# n64-breakout.net
KiCad netlist of a schematic drawn in EAGLE
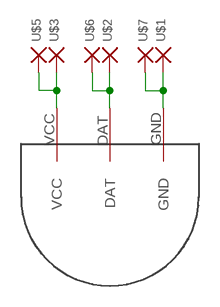
[diagram p0: schematic, sheet 1]

(export (version "E")
  (design (tool "Eeschema 10.0.6"))
  (components
    (comp (ref "U$1")
      (value "SMDPADSMD6080")
      (footprint "eagle-import:SMD6080")
      (libsource (lib "eagle-import") (part "SMDPADSMD6080"))
    )
    (comp (ref "U$2")
      (value "SMDPADSMD6080")
      (footprint "eagle-import:SMD6080")
      (libsource (lib "eagle-import") (part "SMDPADSMD6080"))
    )
    (comp (ref "U$3")
      (value "SMDPADSMD6080")
      (footprint "eagle-import:SMD6080")
      (libsource (lib "eagle-import") (part "SMDPADSMD6080"))
    )
    (comp (ref "U$4")
      (value "N64-CONNECTOR")
      (footprint "eagle-import:N64-CONNECTOR")
      (libsource (lib "eagle-import") (part "N64-CONNECTOR"))
    )
    (comp (ref "U$5")
      (value "SMDPADSMD6080")
      (footprint "eagle-import:SMD6080")
      (libsource (lib "eagle-import") (part "SMDPADSMD6080"))
    )
    (comp (ref "U$6")
      (value "SMDPADSMD6080")
      (footprint "eagle-import:SMD6080")
      (libsource (lib "eagle-import") (part "SMDPADSMD6080"))
    )
    (comp (ref "U$7")
      (value "SMDPADSMD6080")
      (footprint "eagle-import:SMD6080")
      (libsource (lib "eagle-import") (part "SMDPADSMD6080"))
    )
  )
  (nets
    (net (code "1") (name "Net-(U$1-P)") (class "Default")
      (node (ref "U$1") (pin "P$1") (pinfunction "P_P$1") (pintype "passive"))
      (node (ref "U$4") (pin "GND") (pinfunction "GND_GND") (pintype "bidirectional"))
      (node (ref "U$7") (pin "P$1") (pinfunction "P_P$1") (pintype "passive"))
    )
    (net (code "2") (name "Net-(U$2-P)") (class "Default")
      (node (ref "U$2") (pin "P$1") (pinfunction "P_P$1") (pintype "passive"))
      (node (ref "U$4") (pin "DAT") (pinfunction "DAT_DAT") (pintype "bidirectional"))
      (node (ref "U$6") (pin "P$1") (pinfunction "P_P$1") (pintype "passive"))
    )
    (net (code "3") (name "Net-(U$3-P)") (class "Default")
      (node (ref "U$3") (pin "P$1") (pinfunction "P_P$1") (pintype "passive"))
      (node (ref "U$4") (pin "VCC") (pinfunction "VCC_VCC") (pintype "bidirectional"))
      (node (ref "U$5") (pin "P$1") (pinfunction "P_P$1") (pintype "passive"))
    )
  )
)
